# high-power-led-holder.net
KiCad netlist of a schematic drawn in EAGLE
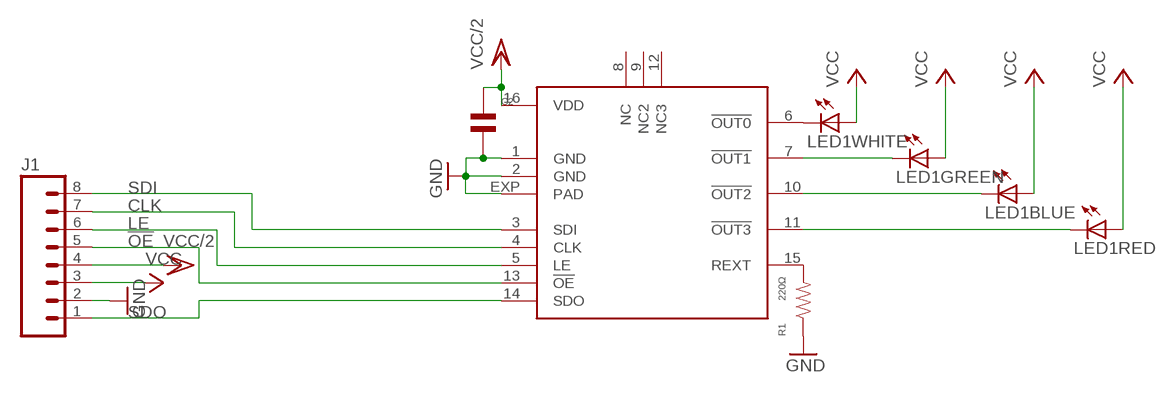
[diagram p0: schematic, sheet 1]

(export (version "E")
  (design (tool "Eeschema 10.0.6"))
  (components
    (comp (ref "C2")
      (value "CAPACITOR_NP_0805")
      (footprint "eagle-import:C0805")
      (libsource (lib "eagle-import") (part "CAPACITOR_NP_0805"))
    )
    (comp (ref "IC1")
      (value "STP04CM05")
      (footprint "eagle-import:TSSOP16L")
      (libsource (lib "eagle-import") (part "STP04CM05"))
    )
    (comp (ref "J1")
      (value "M08")
      (footprint "eagle-import:1X08_ROUND")
      (libsource (lib "eagle-import") (part "M08"))
    )
    (comp (ref "LED1")
      (value "4WLEDBOARD")
      (footprint "eagle-import:4WLEDBOARD")
      (libsource (lib "eagle-import") (part "4WLEDBOARD"))
    )
    (comp (ref "R1")
      (value "220Ω")
      (footprint "eagle-import:R0805")
      (libsource (lib "eagle-import") (part "RESISTOR_0805"))
    )
  )
  (nets
    (net (code "1") (name "/CLK") (class "Default")
      (node (ref "IC1") (pin "4") (pinfunction "CLK_4") (pintype "bidirectional"))
      (node (ref "J1") (pin "7") (pinfunction "7_7") (pintype "passive"))
    )
    (net (code "2") (name "/LE") (class "Default")
      (node (ref "IC1") (pin "5") (pinfunction "LE_5") (pintype "bidirectional"))
      (node (ref "J1") (pin "6") (pinfunction "6_6") (pintype "passive"))
    )
    (net (code "3") (name "/SDI") (class "Default")
      (node (ref "IC1") (pin "3") (pinfunction "SDI_3") (pintype "bidirectional"))
      (node (ref "J1") (pin "8") (pinfunction "8_8") (pintype "passive"))
    )
    (net (code "4") (name "/SDO") (class "Default")
      (node (ref "IC1") (pin "14") (pinfunction "SDO_14") (pintype "bidirectional"))
      (node (ref "J1") (pin "1") (pinfunction "1_1") (pintype "passive"))
    )
    (net (code "5") (name "/~{OE}") (class "Default")
      (node (ref "IC1") (pin "13") (pinfunction "~{OE}_13") (pintype "bidirectional"))
      (node (ref "J1") (pin "5") (pinfunction "5_5") (pintype "passive"))
    )
    (net (code "6") (name "GND") (class "Default")
      (node (ref "C2") (pin "P$2") (pinfunction "P$2_P$2") (pintype "passive"))
      (node (ref "IC1") (pin "1") (pinfunction "GND_1") (pintype "bidirectional"))
      (node (ref "IC1") (pin "2") (pinfunction "GND_2") (pintype "bidirectional"))
      (node (ref "IC1") (pin "EXP") (pinfunction "PAD_EXP") (pintype "bidirectional"))
      (node (ref "J1") (pin "2") (pinfunction "2_2") (pintype "passive"))
      (node (ref "R1") (pin "P$1") (pinfunction "P$1_P$1") (pintype "passive"))
    )
    (net (code "7") (name "Net-(IC1-REXT)") (class "Default")
      (node (ref "IC1") (pin "15") (pinfunction "REXT_15") (pintype "bidirectional"))
      (node (ref "R1") (pin "P$2") (pinfunction "P$2_P$2") (pintype "passive"))
    )
    (net (code "8") (name "Net-(IC1-~{OUT0})") (class "Default")
      (node (ref "IC1") (pin "6") (pinfunction "~{OUT0}_6") (pintype "bidirectional"))
      (node (ref "LED1") (pin "W-") (pinfunction "C_W-") (pintype "passive"))
    )
    (net (code "9") (name "Net-(IC1-~{OUT1})") (class "Default")
      (node (ref "IC1") (pin "7") (pinfunction "~{OUT1}_7") (pintype "bidirectional"))
      (node (ref "LED1") (pin "G-") (pinfunction "C_G-") (pintype "passive"))
    )
    (net (code "10") (name "Net-(IC1-~{OUT2})") (class "Default")
      (node (ref "IC1") (pin "10") (pinfunction "~{OUT2}_10") (pintype "bidirectional"))
      (node (ref "LED1") (pin "B-") (pinfunction "C_B-") (pintype "passive"))
    )
    (net (code "11") (name "Net-(IC1-~{OUT3})") (class "Default")
      (node (ref "IC1") (pin "11") (pinfunction "~{OUT3}_11") (pintype "bidirectional"))
      (node (ref "LED1") (pin "R-") (pinfunction "C_R-") (pintype "passive"))
    )
    (net (code "12") (name "VCC") (class "Default")
      (node (ref "J1") (pin "3") (pinfunction "3_3") (pintype "passive"))
      (node (ref "LED1") (pin "B+") (pinfunction "A_B+") (pintype "passive"))
      (node (ref "LED1") (pin "G+") (pinfunction "A_G+") (pintype "passive"))
      (node (ref "LED1") (pin "R+") (pinfunction "A_R+") (pintype "passive"))
      (node (ref "LED1") (pin "W+") (pinfunction "A_W+") (pintype "passive"))
    )
    (net (code "13") (name "VCC{slash}2") (class "Default")
      (node (ref "C2") (pin "P$1") (pinfunction "P$1_P$1") (pintype "passive"))
      (node (ref "IC1") (pin "16") (pinfunction "VDD_16") (pintype "bidirectional"))
      (node (ref "J1") (pin "4") (pinfunction "4_4") (pintype "passive"))
    )
    (net (code "14") (name "unconnected-(IC1-NC-Pad8)") (class "Default")
      (node (ref "IC1") (pin "8") (pinfunction "NC_8") (pintype "bidirectional"))
    )
    (net (code "15") (name "unconnected-(IC1-NC2-Pad9)") (class "Default")
      (node (ref "IC1") (pin "9") (pinfunction "NC2_9") (pintype "bidirectional"))
    )
    (net (code "16") (name "unconnected-(IC1-NC3-Pad12)") (class "Default")
      (node (ref "IC1") (pin "12") (pinfunction "NC3_12") (pintype "bidirectional"))
    )
  )
)
